# A_Shield.net
KiCad netlist of a schematic drawn in EAGLE
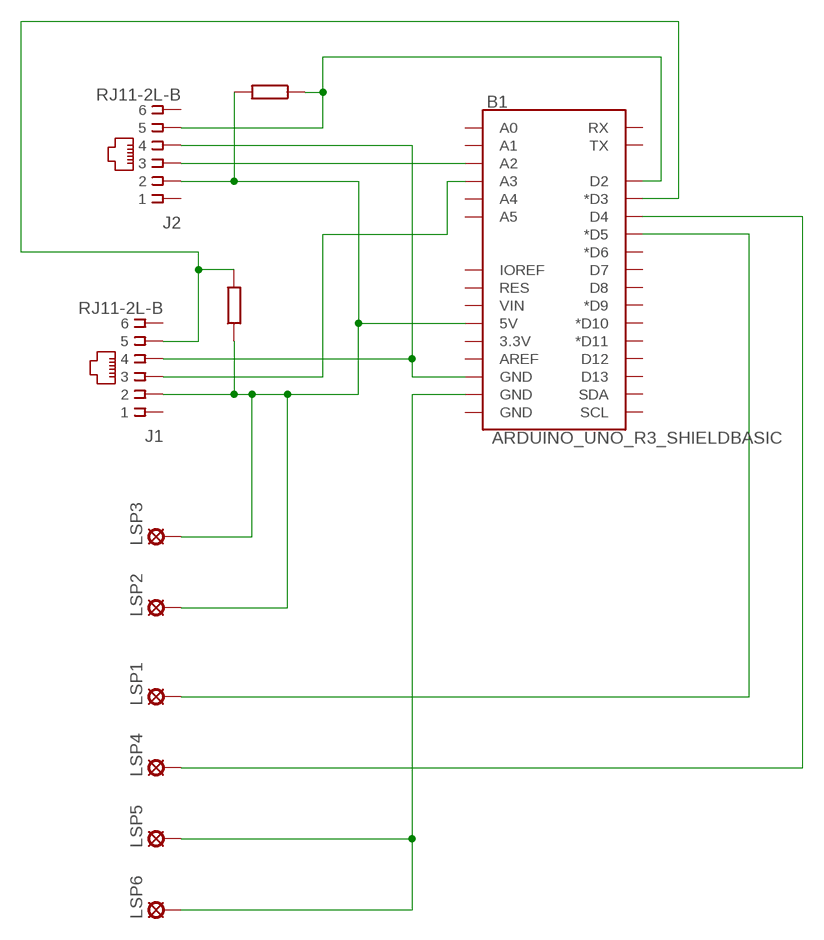
[diagram p0: schematic, sheet 1]

(export (version "E")
  (design (tool "Eeschema 10.0.6"))
  (components
    (comp (ref "B1")
      (value "ARDUINO_UNO_R3_SHIELDBASIC")
      (footprint "eagle-import:UNO_R3_SHIELD")
      (libsource (lib "eagle-import") (part "ARDUINO_UNO_R3_SHIELDBASIC"))
    )
    (comp (ref "J1")
      (value "RJ11-2L-B")
      (footprint "eagle-import:RJ11-NO_SHIELD")
      (fields (field (name "MF") "TYCO ELECTRONICS"))
      (libsource (lib "eagle-import") (part "RJ11-2L-B"))
    )
    (comp (ref "J2")
      (value "RJ11-2L-B")
      (footprint "eagle-import:RJ11-NO_SHIELD")
      (fields (field (name "MF") "TYCO ELECTRONICS"))
      (libsource (lib "eagle-import") (part "RJ11-2L-B"))
    )
    (comp (ref "LSP1")
      (value "LSP13")
      (footprint "eagle-import:LSP13")
      (libsource (lib "eagle-import") (part "LSP13"))
    )
    (comp (ref "LSP2")
      (value "LSP13")
      (footprint "eagle-import:LSP13")
      (libsource (lib "eagle-import") (part "LSP13"))
    )
    (comp (ref "LSP3")
      (value "LSP13")
      (footprint "eagle-import:LSP13")
      (libsource (lib "eagle-import") (part "LSP13"))
    )
    (comp (ref "LSP4")
      (value "LSP13")
      (footprint "eagle-import:LSP13")
      (libsource (lib "eagle-import") (part "LSP13"))
    )
    (comp (ref "LSP5")
      (value "LSP13")
      (footprint "eagle-import:LSP13")
      (libsource (lib "eagle-import") (part "LSP13"))
    )
    (comp (ref "LSP6")
      (value "LSP13")
      (footprint "eagle-import:LSP13")
      (libsource (lib "eagle-import") (part "LSP13"))
    )
  )
  (nets
    (net (code "1") (name "Net-(B1-*D3)") (class "Default")
      (node (ref "B1") (pin "D3") (pinfunction "*D3_D3") (pintype "bidirectional"))
      (node (ref "J1") (pin "5") (pinfunction "5_5") (pintype "passive"))
    )
    (net (code "2") (name "Net-(B1-*D5)") (class "Default")
      (node (ref "B1") (pin "D5") (pinfunction "*D5_D5") (pintype "bidirectional"))
      (node (ref "LSP1") (pin "MP") (pinfunction "MP_MP") (pintype "passive"))
    )
    (net (code "3") (name "Net-(B1-GND-PadGND@1)") (class "Default")
      (node (ref "B1") (pin "GND@1") (pinfunction "GND_GND@1") (pintype "bidirectional"))
      (node (ref "LSP5") (pin "MP") (pinfunction "MP_MP") (pintype "passive"))
      (node (ref "LSP6") (pin "MP") (pinfunction "MP_MP") (pintype "passive"))
    )
    (net (code "4") (name "Net-(B1-GND-PadGND@2)") (class "Default")
      (node (ref "B1") (pin "GND@2") (pinfunction "GND_GND@2") (pintype "bidirectional"))
      (node (ref "J1") (pin "4") (pinfunction "4_4") (pintype "passive"))
      (node (ref "J2") (pin "4") (pinfunction "4_4") (pintype "passive"))
    )
    (net (code "5") (name "Net-(B1-Pad5V)") (class "Default")
      (node (ref "B1") (pin "5V") (pinfunction "5V_5V") (pintype "bidirectional"))
      (node (ref "J1") (pin "2") (pinfunction "2_2") (pintype "passive"))
      (node (ref "J2") (pin "2") (pinfunction "2_2") (pintype "passive"))
      (node (ref "LSP2") (pin "MP") (pinfunction "MP_MP") (pintype "passive"))
      (node (ref "LSP3") (pin "MP") (pinfunction "MP_MP") (pintype "passive"))
    )
    (net (code "6") (name "Net-(B1-PadA2)") (class "Default")
      (node (ref "B1") (pin "A2") (pinfunction "A2_A2") (pintype "bidirectional"))
      (node (ref "J2") (pin "3") (pinfunction "3_3") (pintype "passive"))
    )
    (net (code "7") (name "Net-(B1-PadA3)") (class "Default")
      (node (ref "B1") (pin "A3") (pinfunction "A3_A3") (pintype "bidirectional"))
      (node (ref "J1") (pin "3") (pinfunction "3_3") (pintype "passive"))
    )
    (net (code "8") (name "Net-(B1-PadD2)") (class "Default")
      (node (ref "B1") (pin "D2") (pinfunction "D2_D2") (pintype "bidirectional"))
      (node (ref "J2") (pin "5") (pinfunction "5_5") (pintype "passive"))
    )
    (net (code "9") (name "Net-(B1-PadD4)") (class "Default")
      (node (ref "B1") (pin "D4") (pinfunction "D4_D4") (pintype "bidirectional"))
      (node (ref "LSP4") (pin "MP") (pinfunction "MP_MP") (pintype "passive"))
    )
    (net (code "10") (name "unconnected-(B1-*D6-PadD6)") (class "Default")
      (node (ref "B1") (pin "D6") (pinfunction "*D6_D6") (pintype "bidirectional"))
    )
    (net (code "11") (name "unconnected-(B1-*D9-PadD9)") (class "Default")
      (node (ref "B1") (pin "D9") (pinfunction "*D9_D9") (pintype "bidirectional"))
    )
    (net (code "12") (name "unconnected-(B1-*D10-PadD10)") (class "Default")
      (node (ref "B1") (pin "D10") (pinfunction "*D10_D10") (pintype "bidirectional"))
    )
    (net (code "13") (name "unconnected-(B1-*D11-PadD11)") (class "Default")
      (node (ref "B1") (pin "D11") (pinfunction "*D11_D11") (pintype "bidirectional"))
    )
    (net (code "14") (name "unconnected-(B1-GND-PadGND@0)") (class "Default")
      (node (ref "B1") (pin "GND@0") (pinfunction "GND_GND@0") (pintype "bidirectional"))
    )
    (net (code "15") (name "unconnected-(B1-Pad3.3V)") (class "Default")
      (node (ref "B1") (pin "3.3V") (pinfunction "3.3V_3.3V") (pintype "bidirectional"))
    )
    (net (code "16") (name "unconnected-(B1-PadA0)") (class "Default")
      (node (ref "B1") (pin "A0") (pinfunction "A0_A0") (pintype "bidirectional"))
    )
    (net (code "17") (name "unconnected-(B1-PadA1)") (class "Default")
      (node (ref "B1") (pin "A1") (pinfunction "A1_A1") (pintype "bidirectional"))
    )
    (net (code "18") (name "unconnected-(B1-PadA4)") (class "Default")
      (node (ref "B1") (pin "A4") (pinfunction "A4_A4") (pintype "bidirectional"))
    )
    (net (code "19") (name "unconnected-(B1-PadA5)") (class "Default")
      (node (ref "B1") (pin "A5") (pinfunction "A5_A5") (pintype "bidirectional"))
    )
    (net (code "20") (name "unconnected-(B1-PadAREF)") (class "Default")
      (node (ref "B1") (pin "AREF") (pinfunction "AREF_AREF") (pintype "bidirectional"))
    )
    (net (code "21") (name "unconnected-(B1-PadD7)") (class "Default")
      (node (ref "B1") (pin "D7") (pinfunction "D7_D7") (pintype "bidirectional"))
    )
    (net (code "22") (name "unconnected-(B1-PadD8)") (class "Default")
      (node (ref "B1") (pin "D8") (pinfunction "D8_D8") (pintype "bidirectional"))
    )
    (net (code "23") (name "unconnected-(B1-PadD12)") (class "Default")
      (node (ref "B1") (pin "D12") (pinfunction "D12_D12") (pintype "bidirectional"))
    )
    (net (code "24") (name "unconnected-(B1-PadD13)") (class "Default")
      (node (ref "B1") (pin "D13") (pinfunction "D13_D13") (pintype "bidirectional"))
    )
    (net (code "25") (name "unconnected-(B1-PadIOREF)") (class "Default")
      (node (ref "B1") (pin "IOREF") (pinfunction "IOREF_IOREF") (pintype "bidirectional"))
    )
    (net (code "26") (name "unconnected-(B1-PadRES)") (class "Default")
      (node (ref "B1") (pin "RES") (pinfunction "RES_RES") (pintype "bidirectional"))
    )
    (net (code "27") (name "unconnected-(B1-PadRX)") (class "Default")
      (node (ref "B1") (pin "RX") (pinfunction "RX_RX") (pintype "bidirectional"))
    )
    (net (code "28") (name "unconnected-(B1-PadSCL)") (class "Default")
      (node (ref "B1") (pin "SCL") (pinfunction "SCL_SCL") (pintype "bidirectional"))
    )
    (net (code "29") (name "unconnected-(B1-PadSDA)") (class "Default")
      (node (ref "B1") (pin "SDA") (pinfunction "SDA_SDA") (pintype "bidirectional"))
    )
    (net (code "30") (name "unconnected-(B1-PadTX)") (class "Default")
      (node (ref "B1") (pin "TX") (pinfunction "TX_TX") (pintype "bidirectional"))
    )
    (net (code "31") (name "unconnected-(B1-PadVIN)") (class "Default")
      (node (ref "B1") (pin "VIN") (pinfunction "VIN_VIN") (pintype "bidirectional"))
    )
    (net (code "32") (name "unconnected-(J1-Pad1)") (class "Default")
      (node (ref "J1") (pin "1") (pinfunction "1_1") (pintype "passive"))
    )
    (net (code "33") (name "unconnected-(J1-Pad6)") (class "Default")
      (node (ref "J1") (pin "6") (pinfunction "6_6") (pintype "passive"))
    )
    (net (code "34") (name "unconnected-(J2-Pad1)") (class "Default")
      (node (ref "J2") (pin "1") (pinfunction "1_1") (pintype "passive"))
    )
    (net (code "35") (name "unconnected-(J2-Pad6)") (class "Default")
      (node (ref "J2") (pin "6") (pinfunction "6_6") (pintype "passive"))
    )
  )
)
